# esp_board.net
KiCad netlist of a schematic drawn in EAGLE
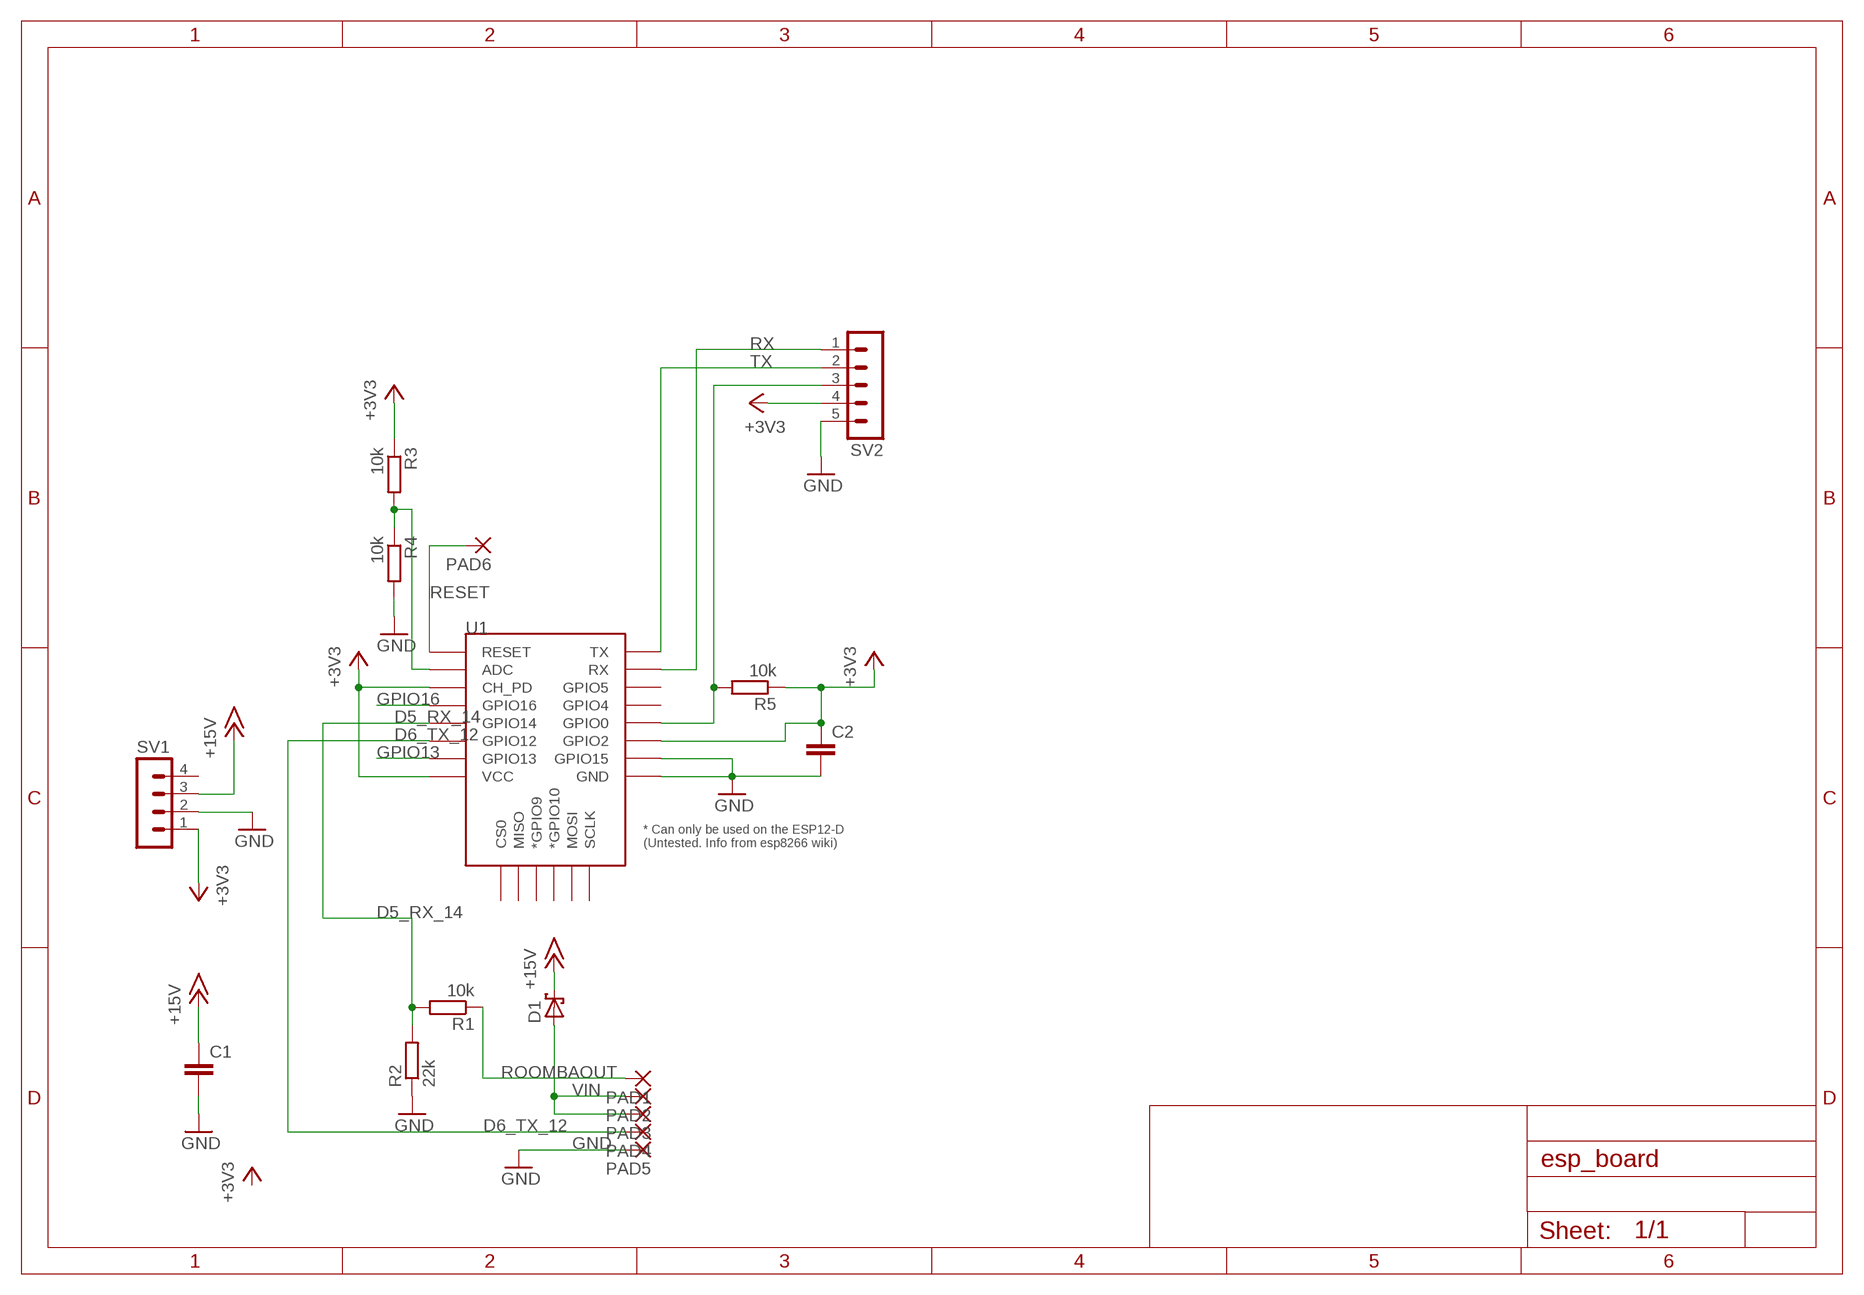
[diagram p0: schematic, sheet 1]

(export (version "E")
  (design (tool "Eeschema 10.0.6"))
  (components
    (comp (ref "C1")
      (value "C-EUC3225")
      (footprint "eagle-import:C3225")
      (libsource (lib "eagle-import") (part "C-EUC3225"))
    )
    (comp (ref "C2")
      (value "C-EUC3225")
      (footprint "eagle-import:C3225")
      (libsource (lib "eagle-import") (part "C-EUC3225"))
    )
    (comp (ref "D1")
      (value "SCHOTTKY-DIODESMC")
      (footprint "eagle-import:SMC")
      (libsource (lib "eagle-import") (part "SCHOTTKY-DIODESMC"))
    )
    (comp (ref "PAD1")
      (value "1,6/0,8")
      (footprint "eagle-import:1,6_0,8")
      (libsource (lib "eagle-import") (part "1,6/0,8"))
    )
    (comp (ref "PAD2")
      (value "1,6/0,8")
      (footprint "eagle-import:1,6_0,8")
      (libsource (lib "eagle-import") (part "1,6/0,8"))
    )
    (comp (ref "PAD3")
      (value "1,6/0,8")
      (footprint "eagle-import:1,6_0,8")
      (libsource (lib "eagle-import") (part "1,6/0,8"))
    )
    (comp (ref "PAD4")
      (value "1,6/0,8")
      (footprint "eagle-import:1,6_0,8")
      (libsource (lib "eagle-import") (part "1,6/0,8"))
    )
    (comp (ref "PAD5")
      (value "1,6/0,8")
      (footprint "eagle-import:1,6_0,8")
      (libsource (lib "eagle-import") (part "1,6/0,8"))
    )
    (comp (ref "PAD6")
      (value "SMD2")
      (footprint "eagle-import:SMD1,27-2,54")
      (libsource (lib "eagle-import") (part "SMD2"))
    )
    (comp (ref "R1")
      (value "10k")
      (footprint "eagle-import:R0805")
      (libsource (lib "eagle-import") (part "R-EU_R0805"))
    )
    (comp (ref "R2")
      (value "22k")
      (footprint "eagle-import:R0805")
      (libsource (lib "eagle-import") (part "R-EU_R0805"))
    )
    (comp (ref "R3")
      (value "10k")
      (footprint "eagle-import:R0805")
      (libsource (lib "eagle-import") (part "R-EU_R0805"))
    )
    (comp (ref "R4")
      (value "10k")
      (footprint "eagle-import:R0805")
      (libsource (lib "eagle-import") (part "R-EU_R0805"))
    )
    (comp (ref "R5")
      (value "10k")
      (footprint "eagle-import:R0805")
      (libsource (lib "eagle-import") (part "R-EU_R0805"))
    )
    (comp (ref "SV1")
      (value "MA04-1")
      (footprint "eagle-import:MA04-1")
      (libsource (lib "eagle-import") (part "MA04-1"))
    )
    (comp (ref "SV2")
      (value "MA05-1")
      (footprint "eagle-import:MA05-1")
      (libsource (lib "eagle-import") (part "MA05-1"))
    )
    (comp (ref "U1")
      (value "ESP12ESMD")
      (footprint "eagle-import:ESP12E-SMD")
      (libsource (lib "eagle-import") (part "ESP12ESMD"))
    )
  )
  (nets
    (net (code "1") (name "+3V3") (class "Default")
      (node (ref "C2") (pin "1") (pinfunction "1_1") (pintype "passive"))
      (node (ref "R3") (pin "1") (pinfunction "1_1") (pintype "passive"))
      (node (ref "R5") (pin "1") (pinfunction "1_1") (pintype "passive"))
      (node (ref "SV1") (pin "1") (pinfunction "1_1") (pintype "passive"))
      (node (ref "SV2") (pin "4") (pinfunction "4_4") (pintype "passive"))
      (node (ref "U1") (pin "CH_PD") (pinfunction "CH_PD_CH_PD") (pintype "bidirectional"))
      (node (ref "U1") (pin "GPIO2") (pinfunction "GPIO2_GPIO2") (pintype "bidirectional"))
      (node (ref "U1") (pin "VCC") (pinfunction "VCC_VCC") (pintype "bidirectional"))
    )
    (net (code "2") (name "+15V") (class "Default")
      (node (ref "C1") (pin "1") (pinfunction "1_1") (pintype "passive"))
      (node (ref "D1") (pin "C") (pinfunction "C_C") (pintype "passive"))
      (node (ref "SV1") (pin "3") (pinfunction "3_3") (pintype "passive"))
    )
    (net (code "3") (name "/D5_RX_14") (class "Default")
      (node (ref "R1") (pin "2") (pinfunction "2_2") (pintype "passive"))
      (node (ref "R2") (pin "2") (pinfunction "2_2") (pintype "passive"))
      (node (ref "U1") (pin "GPIO14") (pinfunction "GPIO14_GPIO14") (pintype "bidirectional"))
    )
    (net (code "4") (name "/D6_TX_12") (class "Default")
      (node (ref "PAD4") (pin "1") (pinfunction "P_1") (pintype "passive"))
      (node (ref "U1") (pin "GPIO12") (pinfunction "GPIO12_GPIO12") (pintype "bidirectional"))
    )
    (net (code "5") (name "/GPIO13") (class "Default")
      (node (ref "U1") (pin "GPIO13") (pinfunction "GPIO13_GPIO13") (pintype "bidirectional"))
    )
    (net (code "6") (name "/GPIO16") (class "Default")
      (node (ref "U1") (pin "GPIO16") (pinfunction "GPIO16_GPIO16") (pintype "bidirectional"))
    )
    (net (code "7") (name "/RESET") (class "Default")
      (node (ref "PAD6") (pin "1") (pinfunction "P_1") (pintype "passive"))
      (node (ref "U1") (pin "RESET") (pinfunction "RESET_RESET") (pintype "bidirectional"))
    )
    (net (code "8") (name "/ROOMBAOUT") (class "Default")
      (node (ref "PAD1") (pin "1") (pinfunction "P_1") (pintype "passive"))
      (node (ref "R1") (pin "1") (pinfunction "1_1") (pintype "passive"))
    )
    (net (code "9") (name "/RX") (class "Default")
      (node (ref "SV2") (pin "1") (pinfunction "1_1") (pintype "passive"))
      (node (ref "U1") (pin "RXD0") (pinfunction "RX_RXD0") (pintype "bidirectional"))
    )
    (net (code "10") (name "/TX") (class "Default")
      (node (ref "SV2") (pin "2") (pinfunction "2_2") (pintype "passive"))
      (node (ref "U1") (pin "TXD0") (pinfunction "TX_TXD0") (pintype "bidirectional"))
    )
    (net (code "11") (name "/VIN") (class "Default")
      (node (ref "D1") (pin "A") (pinfunction "A_A") (pintype "passive"))
      (node (ref "PAD2") (pin "1") (pinfunction "P_1") (pintype "passive"))
      (node (ref "PAD3") (pin "1") (pinfunction "P_1") (pintype "passive"))
    )
    (net (code "12") (name "GND") (class "Default")
      (node (ref "C1") (pin "2") (pinfunction "2_2") (pintype "passive"))
      (node (ref "C2") (pin "2") (pinfunction "2_2") (pintype "passive"))
      (node (ref "PAD5") (pin "1") (pinfunction "P_1") (pintype "passive"))
      (node (ref "R2") (pin "1") (pinfunction "1_1") (pintype "passive"))
      (node (ref "R4") (pin "2") (pinfunction "2_2") (pintype "passive"))
      (node (ref "SV1") (pin "2") (pinfunction "2_2") (pintype "passive"))
      (node (ref "SV2") (pin "5") (pinfunction "5_5") (pintype "passive"))
      (node (ref "U1") (pin "GND") (pinfunction "GND_GND") (pintype "bidirectional"))
      (node (ref "U1") (pin "GPIO15") (pinfunction "GPIO15_GPIO15") (pintype "bidirectional"))
    )
    (net (code "13") (name "Net-(R3-Pad2)") (class "Default")
      (node (ref "R3") (pin "2") (pinfunction "2_2") (pintype "passive"))
      (node (ref "R4") (pin "1") (pinfunction "1_1") (pintype "passive"))
      (node (ref "U1") (pin "ADC") (pinfunction "ADC_ADC") (pintype "bidirectional"))
    )
    (net (code "14") (name "Net-(R5-Pad2)") (class "Default")
      (node (ref "R5") (pin "2") (pinfunction "2_2") (pintype "passive"))
      (node (ref "SV2") (pin "3") (pinfunction "3_3") (pintype "passive"))
      (node (ref "U1") (pin "GPIO0") (pinfunction "GPIO0_GPIO0") (pintype "bidirectional"))
    )
    (net (code "15") (name "unconnected-(SV1-Pad4)") (class "Default")
      (node (ref "SV1") (pin "4") (pinfunction "4_4") (pintype "passive"))
    )
    (net (code "16") (name "unconnected-(U1-*GPIO9-PadGPIO9)") (class "Default")
      (node (ref "U1") (pin "GPIO9") (pinfunction "*GPIO9_GPIO9") (pintype "bidirectional"))
    )
    (net (code "17") (name "unconnected-(U1-*GPIO10-PadGPIO10)") (class "Default")
      (node (ref "U1") (pin "GPIO10") (pinfunction "*GPIO10_GPIO10") (pintype "bidirectional"))
    )
    (net (code "18") (name "unconnected-(U1-PadCS0)") (class "Default")
      (node (ref "U1") (pin "CS0") (pinfunction "CS0_CS0") (pintype "bidirectional"))
    )
    (net (code "19") (name "unconnected-(U1-PadGPIO4)") (class "Default")
      (node (ref "U1") (pin "GPIO4") (pinfunction "GPIO4_GPIO4") (pintype "bidirectional"))
    )
    (net (code "20") (name "unconnected-(U1-PadGPIO5)") (class "Default")
      (node (ref "U1") (pin "GPIO5") (pinfunction "GPIO5_GPIO5") (pintype "bidirectional"))
    )
    (net (code "21") (name "unconnected-(U1-PadMISO)") (class "Default")
      (node (ref "U1") (pin "MISO") (pinfunction "MISO_MISO") (pintype "bidirectional"))
    )
    (net (code "22") (name "unconnected-(U1-PadMOSI)") (class "Default")
      (node (ref "U1") (pin "MOSI") (pinfunction "MOSI_MOSI") (pintype "bidirectional"))
    )
    (net (code "23") (name "unconnected-(U1-PadSCLK)") (class "Default")
      (node (ref "U1") (pin "SCLK") (pinfunction "SCLK_SCLK") (pintype "bidirectional"))
    )
  )
)
